# MicroSDCard.net
KiCad netlist of a schematic drawn in Altium Designer
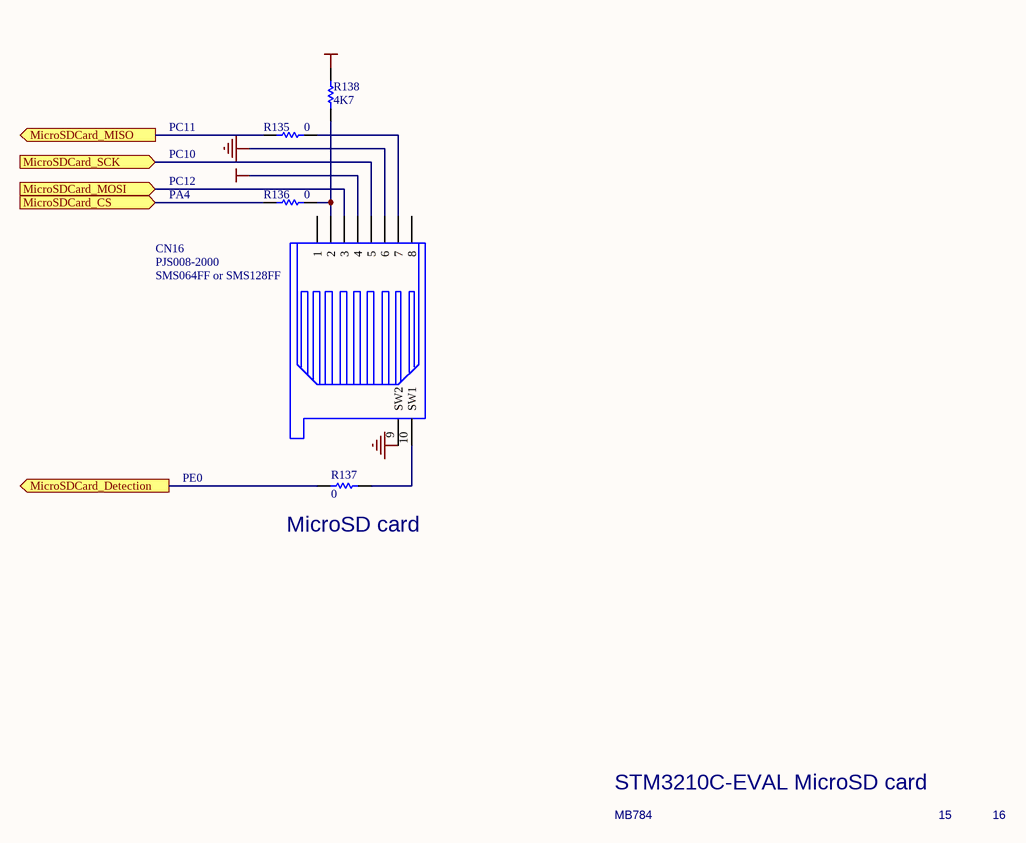
[diagram p0: MicroSDCard.SchDoc]

(export (version "E")
  (design (tool "Eeschema 10.0.6"))
  (components
    (comp (ref "CN16")
      (value "PJS008-2000")
      (footprint "MSD(PJS008)")
      (libsource (lib "MB525") (part "SMS016AFA5E"))
    )
    (comp (ref "R135")
      (value "0")
      (footprint "0603R")
      (description "Resistor")
      (fields (field (name "PUBLISHER") "Altium Limited"))
      (libsource (lib "Miscellaneous Devices") (part "Res1"))
    )
    (comp (ref "R136")
      (value "0")
      (footprint "0603R")
      (description "Resistor")
      (fields (field (name "PUBLISHER") "Altium Limited"))
      (libsource (lib "Miscellaneous Devices") (part "Res1"))
    )
    (comp (ref "R137")
      (value "0")
      (footprint "0603R")
      (description "Resistor")
      (fields (field (name "PUBLISHER") "Altium Limited"))
      (libsource (lib "Miscellaneous Devices") (part "Res1"))
    )
    (comp (ref "R138")
      (value "4K7")
      (footprint "0603R")
      (description "Resistor")
      (fields (field (name "PUBLISHER") "Altium Limited"))
      (libsource (lib "Miscellaneous Devices") (part "Res1"))
    )
  )
  (nets
    (net (code "1") (name "+3V3") (class "Default")
      (node (ref "CN16") (pin "4") (pinfunction "4_4") (pintype "passive"))
      (node (ref "R138") (pin "2") (pinfunction "2_2") (pintype "passive"))
    )
    (net (code "2") (name "/MicroSDCard_CS") (class "Default")
      (node (ref "R136") (pin "2") (pinfunction "2_2") (pintype "passive"))
    )
    (net (code "3") (name "/MicroSDCard_Detection") (class "Default")
      (node (ref "R137") (pin "1") (pinfunction "1_1") (pintype "passive"))
    )
    (net (code "4") (name "/MicroSDCard_MISO") (class "Default")
      (node (ref "R135") (pin "1") (pinfunction "1_1") (pintype "passive"))
    )
    (net (code "5") (name "/MicroSDCard_MOSI") (class "Default")
      (node (ref "CN16") (pin "3") (pinfunction "3_3") (pintype "passive"))
    )
    (net (code "6") (name "/MicroSDCard_SCK") (class "Default")
      (node (ref "CN16") (pin "5") (pinfunction "5_5") (pintype "passive"))
    )
    (net (code "7") (name "GND") (class "Default")
      (node (ref "CN16") (pin "6") (pinfunction "6_6") (pintype "passive"))
      (node (ref "CN16") (pin "9") (pinfunction "SW2_9") (pintype "passive"))
    )
    (net (code "8") (name "Net-(CN16-Pad2)") (class "Default")
      (node (ref "CN16") (pin "2") (pinfunction "2_2") (pintype "passive"))
      (node (ref "R136") (pin "1") (pinfunction "1_1") (pintype "passive"))
      (node (ref "R138") (pin "1") (pinfunction "1_1") (pintype "passive"))
    )
    (net (code "9") (name "Net-(CN16-Pad7)") (class "Default")
      (node (ref "CN16") (pin "7") (pinfunction "7_7") (pintype "passive"))
      (node (ref "R135") (pin "2") (pinfunction "2_2") (pintype "passive"))
    )
    (net (code "10") (name "Net-(CN16-SW1)") (class "Default")
      (node (ref "CN16") (pin "10") (pinfunction "SW1_10") (pintype "passive"))
      (node (ref "R137") (pin "2") (pinfunction "2_2") (pintype "passive"))
    )
    (net (code "11") (name "unconnected-(CN16-Pad1)") (class "Default")
      (node (ref "CN16") (pin "1") (pinfunction "1_1") (pintype "passive"))
    )
    (net (code "12") (name "unconnected-(CN16-Pad8)") (class "Default")
      (node (ref "CN16") (pin "8") (pinfunction "8_8") (pintype "passive"))
    )
  )
)
